# Macropad_BMS.net
KiCad netlist of a schematic drawn in EAGLE
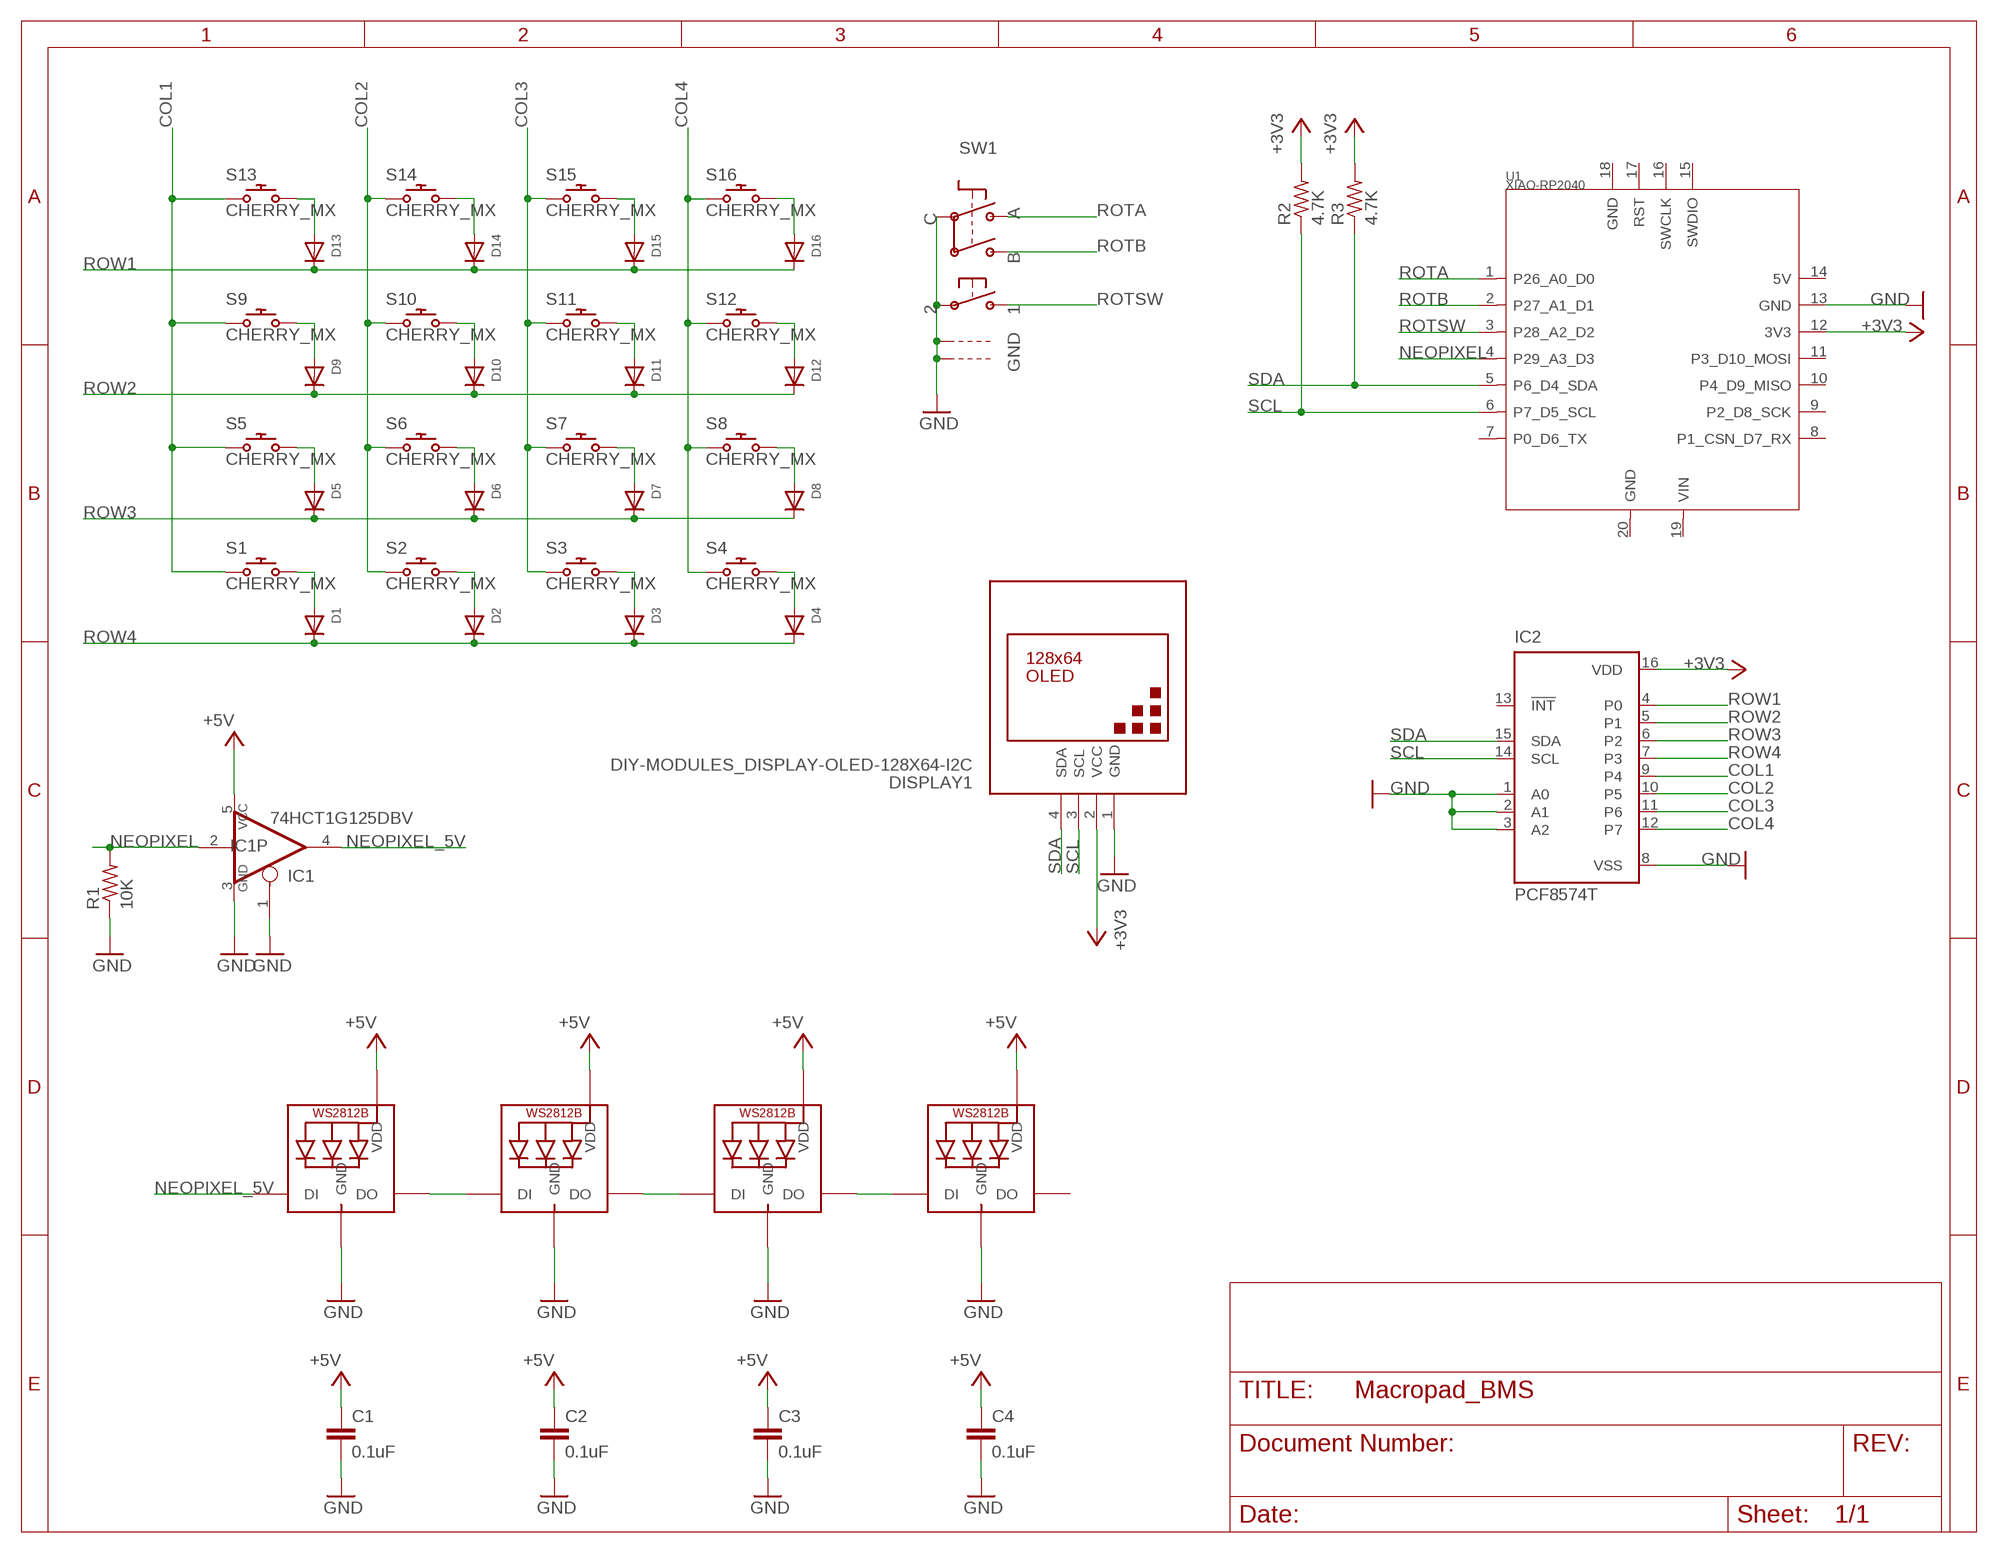
[diagram p0: schematic, sheet 1]

(export (version "E")
  (design (tool "Eeschema 10.0.6"))
  (components
    (comp (ref "C1")
      (value "0.1uF")
      (footprint "eagle-import:0603")
      (libsource (lib "eagle-import") (part "0.1UF-0603-25V-(+80/-20%)"))
    )
    (comp (ref "C2")
      (value "0.1uF")
      (footprint "eagle-import:0603")
      (libsource (lib "eagle-import") (part "0.1UF-0603-25V-(+80/-20%)"))
    )
    (comp (ref "C3")
      (value "0.1uF")
      (footprint "eagle-import:0603")
      (libsource (lib "eagle-import") (part "0.1UF-0603-25V-(+80/-20%)"))
    )
    (comp (ref "C4")
      (value "0.1uF")
      (footprint "eagle-import:0603")
      (libsource (lib "eagle-import") (part "0.1UF-0603-25V-(+80/-20%)"))
    )
    (comp (ref "D1")
      (value "MICROBUILDER_DIODESOD-123")
      (footprint "eagle-import:MICROBUILDER_SOD-123")
      (libsource (lib "eagle-import") (part "MICROBUILDER_DIODESOD-123"))
    )
    (comp (ref "D2")
      (value "MICROBUILDER_DIODESOD-123")
      (footprint "eagle-import:MICROBUILDER_SOD-123")
      (libsource (lib "eagle-import") (part "MICROBUILDER_DIODESOD-123"))
    )
    (comp (ref "D3")
      (value "MICROBUILDER_DIODESOD-123")
      (footprint "eagle-import:MICROBUILDER_SOD-123")
      (libsource (lib "eagle-import") (part "MICROBUILDER_DIODESOD-123"))
    )
    (comp (ref "D4")
      (value "MICROBUILDER_DIODESOD-123")
      (footprint "eagle-import:MICROBUILDER_SOD-123")
      (libsource (lib "eagle-import") (part "MICROBUILDER_DIODESOD-123"))
    )
    (comp (ref "D5")
      (value "MICROBUILDER_DIODESOD-123")
      (footprint "eagle-import:MICROBUILDER_SOD-123")
      (libsource (lib "eagle-import") (part "MICROBUILDER_DIODESOD-123"))
    )
    (comp (ref "D6")
      (value "MICROBUILDER_DIODESOD-123")
      (footprint "eagle-import:MICROBUILDER_SOD-123")
      (libsource (lib "eagle-import") (part "MICROBUILDER_DIODESOD-123"))
    )
    (comp (ref "D7")
      (value "MICROBUILDER_DIODESOD-123")
      (footprint "eagle-import:MICROBUILDER_SOD-123")
      (libsource (lib "eagle-import") (part "MICROBUILDER_DIODESOD-123"))
    )
    (comp (ref "D8")
      (value "MICROBUILDER_DIODESOD-123")
      (footprint "eagle-import:MICROBUILDER_SOD-123")
      (libsource (lib "eagle-import") (part "MICROBUILDER_DIODESOD-123"))
    )
    (comp (ref "D9")
      (value "MICROBUILDER_DIODESOD-123")
      (footprint "eagle-import:MICROBUILDER_SOD-123")
      (libsource (lib "eagle-import") (part "MICROBUILDER_DIODESOD-123"))
    )
    (comp (ref "D10")
      (value "MICROBUILDER_DIODESOD-123")
      (footprint "eagle-import:MICROBUILDER_SOD-123")
      (libsource (lib "eagle-import") (part "MICROBUILDER_DIODESOD-123"))
    )
    (comp (ref "D11")
      (value "MICROBUILDER_DIODESOD-123")
      (footprint "eagle-import:MICROBUILDER_SOD-123")
      (libsource (lib "eagle-import") (part "MICROBUILDER_DIODESOD-123"))
    )
    (comp (ref "D12")
      (value "MICROBUILDER_DIODESOD-123")
      (footprint "eagle-import:MICROBUILDER_SOD-123")
      (libsource (lib "eagle-import") (part "MICROBUILDER_DIODESOD-123"))
    )
    (comp (ref "D13")
      (value "MICROBUILDER_DIODESOD-123")
      (footprint "eagle-import:MICROBUILDER_SOD-123")
      (libsource (lib "eagle-import") (part "MICROBUILDER_DIODESOD-123"))
    )
    (comp (ref "D14")
      (value "MICROBUILDER_DIODESOD-123")
      (footprint "eagle-import:MICROBUILDER_SOD-123")
      (libsource (lib "eagle-import") (part "MICROBUILDER_DIODESOD-123"))
    )
    (comp (ref "D15")
      (value "MICROBUILDER_DIODESOD-123")
      (footprint "eagle-import:MICROBUILDER_SOD-123")
      (libsource (lib "eagle-import") (part "MICROBUILDER_DIODESOD-123"))
    )
    (comp (ref "D16")
      (value "MICROBUILDER_DIODESOD-123")
      (footprint "eagle-import:MICROBUILDER_SOD-123")
      (libsource (lib "eagle-import") (part "MICROBUILDER_DIODESOD-123"))
    )
    (comp (ref "DISPLAY1")
      (value "DIY-MODULES_DISPLAY-OLED-128X64-I2C")
      (footprint "eagle-import:DIY-MODULES_DISPLAY-OLED-128X64-I2C")
      (libsource (lib "eagle-import") (part "DIY-MODULES_DISPLAY-OLED-128X64-I2C"))
    )
    (comp (ref "IC1")
      (value "74HCT1G125DBV")
      (footprint "eagle-import:SOT23-5")
      (libsource (lib "eagle-import") (part "741G125DBVAHC"))
    )
    (comp (ref "IC2")
      (value "PCF8574T")
      (footprint "eagle-import:SO16W")
      (fields (field (name "MPN") "PCF8574T/3,512"))
      (libsource (lib "eagle-import") (part "PCF8574T"))
    )
    (comp (ref "LED1")
      (value "WS2812B5050")
      (footprint "eagle-import:WS2812B")
      (libsource (lib "eagle-import") (part "WS2812B5050"))
    )
    (comp (ref "LED2")
      (value "WS2812B5050")
      (footprint "eagle-import:WS2812B")
      (libsource (lib "eagle-import") (part "WS2812B5050"))
    )
    (comp (ref "LED3")
      (value "WS2812B5050")
      (footprint "eagle-import:WS2812B")
      (libsource (lib "eagle-import") (part "WS2812B5050"))
    )
    (comp (ref "LED4")
      (value "WS2812B5050")
      (footprint "eagle-import:WS2812B")
      (libsource (lib "eagle-import") (part "WS2812B5050"))
    )
    (comp (ref "R1")
      (value "10K")
      (footprint "eagle-import:R0805")
      (libsource (lib "eagle-import") (part "R-US_R0805"))
    )
    (comp (ref "R2")
      (value "4.7K")
      (footprint "eagle-import:R0805")
      (libsource (lib "eagle-import") (part "R-US_R0805"))
    )
    (comp (ref "R3")
      (value "4.7K")
      (footprint "eagle-import:R0805")
      (libsource (lib "eagle-import") (part "R-US_R0805"))
    )
    (comp (ref "S1")
      (value "CHERRY_MX")
      (footprint "eagle-import:CHERRY_MX")
      (libsource (lib "eagle-import") (part "CHERRY_MX"))
    )
    (comp (ref "S2")
      (value "CHERRY_MX")
      (footprint "eagle-import:CHERRY_MX")
      (libsource (lib "eagle-import") (part "CHERRY_MX"))
    )
    (comp (ref "S3")
      (value "CHERRY_MX")
      (footprint "eagle-import:CHERRY_MX")
      (libsource (lib "eagle-import") (part "CHERRY_MX"))
    )
    (comp (ref "S4")
      (value "CHERRY_MX")
      (footprint "eagle-import:CHERRY_MX")
      (libsource (lib "eagle-import") (part "CHERRY_MX"))
    )
    (comp (ref "S5")
      (value "CHERRY_MX")
      (footprint "eagle-import:CHERRY_MX")
      (libsource (lib "eagle-import") (part "CHERRY_MX"))
    )
    (comp (ref "S6")
      (value "CHERRY_MX")
      (footprint "eagle-import:CHERRY_MX")
      (libsource (lib "eagle-import") (part "CHERRY_MX"))
    )
    (comp (ref "S7")
      (value "CHERRY_MX")
      (footprint "eagle-import:CHERRY_MX")
      (libsource (lib "eagle-import") (part "CHERRY_MX"))
    )
    (comp (ref "S8")
      (value "CHERRY_MX")
      (footprint "eagle-import:CHERRY_MX")
      (libsource (lib "eagle-import") (part "CHERRY_MX"))
    )
    (comp (ref "S9")
      (value "CHERRY_MX")
      (footprint "eagle-import:CHERRY_MX")
      (libsource (lib "eagle-import") (part "CHERRY_MX"))
    )
    (comp (ref "S10")
      (value "CHERRY_MX")
      (footprint "eagle-import:CHERRY_MX")
      (libsource (lib "eagle-import") (part "CHERRY_MX"))
    )
    (comp (ref "S11")
      (value "CHERRY_MX")
      (footprint "eagle-import:CHERRY_MX")
      (libsource (lib "eagle-import") (part "CHERRY_MX"))
    )
    (comp (ref "S12")
      (value "CHERRY_MX")
      (footprint "eagle-import:CHERRY_MX")
      (libsource (lib "eagle-import") (part "CHERRY_MX"))
    )
    (comp (ref "S13")
      (value "CHERRY_MX")
      (footprint "eagle-import:CHERRY_MX")
      (libsource (lib "eagle-import") (part "CHERRY_MX"))
    )
    (comp (ref "S14")
      (value "CHERRY_MX")
      (footprint "eagle-import:CHERRY_MX")
      (libsource (lib "eagle-import") (part "CHERRY_MX"))
    )
    (comp (ref "S15")
      (value "CHERRY_MX")
      (footprint "eagle-import:CHERRY_MX")
      (libsource (lib "eagle-import") (part "CHERRY_MX"))
    )
    (comp (ref "S16")
      (value "CHERRY_MX")
      (footprint "eagle-import:CHERRY_MX")
      (libsource (lib "eagle-import") (part "CHERRY_MX"))
    )
    (comp (ref "SW1")
      (value "ADAFRUIT_ELECTROMECH_ENCODER_PLUS_SWITCH_BOURNS_PEC11")
      (footprint "eagle-import:ADAFRUIT_ELECTROMECH_PEC11+SWITCH")
      (libsource (lib "eagle-import") (part "ADAFRUIT_ELECTROMECH_ENCODER_PLUS_SWITCH_PEC11_BOURNS"))
    )
    (comp (ref "U1")
      (value "XIAO-RP2040")
      (footprint "eagle-import:XIAO-SAMD21_RP2040-MODULE14P-2.54-21X17.8MM")
      (libsource (lib "eagle-import") (part "XIAO-RP2040"))
    )
  )
  (nets
    (net (code "1") (name "+3V3") (class "Default")
      (node (ref "DISPLAY1") (pin "2") (pinfunction "VCC_2") (pintype "bidirectional"))
      (node (ref "IC2") (pin "16") (pinfunction "VDD_16") (pintype "power_in"))
      (node (ref "R2") (pin "2") (pinfunction "2_2") (pintype "passive"))
      (node (ref "R3") (pin "2") (pinfunction "2_2") (pintype "passive"))
      (node (ref "U1") (pin "12") (pinfunction "3V3_12") (pintype "bidirectional"))
    )
    (net (code "2") (name "+5V") (class "Default")
      (node (ref "C1") (pin "1") (pinfunction "1_1") (pintype "passive"))
      (node (ref "C2") (pin "1") (pinfunction "1_1") (pintype "passive"))
      (node (ref "C3") (pin "1") (pinfunction "1_1") (pintype "passive"))
      (node (ref "C4") (pin "1") (pinfunction "1_1") (pintype "passive"))
      (node (ref "IC1") (pin "5") (pinfunction "VCC_5") (pintype "power_in"))
      (node (ref "LED1") (pin "1-VDD") (pinfunction "VDD_1-VDD") (pintype "power_in"))
      (node (ref "LED2") (pin "1-VDD") (pinfunction "VDD_1-VDD") (pintype "power_in"))
      (node (ref "LED3") (pin "1-VDD") (pinfunction "VDD_1-VDD") (pintype "power_in"))
      (node (ref "LED4") (pin "1-VDD") (pinfunction "VDD_1-VDD") (pintype "power_in"))
    )
    (net (code "3") (name "/COL1") (class "Default")
      (node (ref "IC2") (pin "9") (pinfunction "P4_9") (pintype "bidirectional"))
      (node (ref "S1") (pin "S1") (pinfunction "1_S1") (pintype "passive"))
      (node (ref "S13") (pin "S1") (pinfunction "1_S1") (pintype "passive"))
      (node (ref "S5") (pin "S1") (pinfunction "1_S1") (pintype "passive"))
      (node (ref "S9") (pin "S1") (pinfunction "1_S1") (pintype "passive"))
    )
    (net (code "4") (name "/COL2") (class "Default")
      (node (ref "IC2") (pin "10") (pinfunction "P5_10") (pintype "bidirectional"))
      (node (ref "S10") (pin "S1") (pinfunction "1_S1") (pintype "passive"))
      (node (ref "S14") (pin "S1") (pinfunction "1_S1") (pintype "passive"))
      (node (ref "S2") (pin "S1") (pinfunction "1_S1") (pintype "passive"))
      (node (ref "S6") (pin "S1") (pinfunction "1_S1") (pintype "passive"))
    )
    (net (code "5") (name "/COL3") (class "Default")
      (node (ref "IC2") (pin "11") (pinfunction "P6_11") (pintype "bidirectional"))
      (node (ref "S11") (pin "S1") (pinfunction "1_S1") (pintype "passive"))
      (node (ref "S15") (pin "S1") (pinfunction "1_S1") (pintype "passive"))
      (node (ref "S3") (pin "S1") (pinfunction "1_S1") (pintype "passive"))
      (node (ref "S7") (pin "S1") (pinfunction "1_S1") (pintype "passive"))
    )
    (net (code "6") (name "/COL4") (class "Default")
      (node (ref "IC2") (pin "12") (pinfunction "P7_12") (pintype "bidirectional"))
      (node (ref "S12") (pin "S1") (pinfunction "1_S1") (pintype "passive"))
      (node (ref "S16") (pin "S1") (pinfunction "1_S1") (pintype "passive"))
      (node (ref "S4") (pin "S1") (pinfunction "1_S1") (pintype "passive"))
      (node (ref "S8") (pin "S1") (pinfunction "1_S1") (pintype "passive"))
    )
    (net (code "7") (name "/NEOPIXEL") (class "Default")
      (node (ref "IC1") (pin "2") (pinfunction "I_2") (pintype "input"))
      (node (ref "R1") (pin "2") (pinfunction "2_2") (pintype "passive"))
      (node (ref "U1") (pin "4") (pinfunction "P29_A3_D3_4") (pintype "bidirectional"))
    )
    (net (code "8") (name "/NEOPIXEL_5V") (class "Default")
      (node (ref "IC1") (pin "4") (pinfunction "O_4") (pintype "tri_state"))
      (node (ref "LED1") (pin "4-DIN") (pinfunction "DI_4-DIN") (pintype "input"))
    )
    (net (code "9") (name "/ROTA") (class "Default")
      (node (ref "SW1") (pin "P$A") (pinfunction "P$A_P$A") (pintype "passive"))
      (node (ref "U1") (pin "1") (pinfunction "P26_A0_D0_1") (pintype "bidirectional"))
    )
    (net (code "10") (name "/ROTB") (class "Default")
      (node (ref "SW1") (pin "P$B") (pinfunction "P$B_P$B") (pintype "passive"))
      (node (ref "U1") (pin "2") (pinfunction "P27_A1_D1_2") (pintype "bidirectional"))
    )
    (net (code "11") (name "/ROTSW") (class "Default")
      (node (ref "SW1") (pin "P$1") (pinfunction "P$1_P$1") (pintype "passive"))
      (node (ref "U1") (pin "3") (pinfunction "P28_A2_D2_3") (pintype "bidirectional"))
    )
    (net (code "12") (name "/ROW1") (class "Default")
      (node (ref "D13") (pin "C") (pinfunction "C_C") (pintype "passive"))
      (node (ref "D14") (pin "C") (pinfunction "C_C") (pintype "passive"))
      (node (ref "D15") (pin "C") (pinfunction "C_C") (pintype "passive"))
      (node (ref "D16") (pin "C") (pinfunction "C_C") (pintype "passive"))
      (node (ref "IC2") (pin "4") (pinfunction "P0_4") (pintype "bidirectional"))
    )
    (net (code "13") (name "/ROW2") (class "Default")
      (node (ref "D10") (pin "C") (pinfunction "C_C") (pintype "passive"))
      (node (ref "D11") (pin "C") (pinfunction "C_C") (pintype "passive"))
      (node (ref "D12") (pin "C") (pinfunction "C_C") (pintype "passive"))
      (node (ref "D9") (pin "C") (pinfunction "C_C") (pintype "passive"))
      (node (ref "IC2") (pin "5") (pinfunction "P1_5") (pintype "bidirectional"))
    )
    (net (code "14") (name "/ROW3") (class "Default")
      (node (ref "D5") (pin "C") (pinfunction "C_C") (pintype "passive"))
      (node (ref "D6") (pin "C") (pinfunction "C_C") (pintype "passive"))
      (node (ref "D7") (pin "C") (pinfunction "C_C") (pintype "passive"))
      (node (ref "D8") (pin "C") (pinfunction "C_C") (pintype "passive"))
      (node (ref "IC2") (pin "6") (pinfunction "P2_6") (pintype "bidirectional"))
    )
    (net (code "15") (name "/ROW4") (class "Default")
      (node (ref "D1") (pin "C") (pinfunction "C_C") (pintype "passive"))
      (node (ref "D2") (pin "C") (pinfunction "C_C") (pintype "passive"))
      (node (ref "D3") (pin "C") (pinfunction "C_C") (pintype "passive"))
      (node (ref "D4") (pin "C") (pinfunction "C_C") (pintype "passive"))
      (node (ref "IC2") (pin "7") (pinfunction "P3_7") (pintype "bidirectional"))
    )
    (net (code "16") (name "/SCL") (class "Default")
      (node (ref "DISPLAY1") (pin "3") (pinfunction "SCL_3") (pintype "bidirectional"))
      (node (ref "IC2") (pin "14") (pinfunction "SCL_14") (pintype "input"))
      (node (ref "R2") (pin "1") (pinfunction "1_1") (pintype "passive"))
      (node (ref "U1") (pin "6") (pinfunction "P7_D5_SCL_6") (pintype "bidirectional"))
    )
    (net (code "17") (name "/SDA") (class "Default")
      (node (ref "DISPLAY1") (pin "4") (pinfunction "SDA_4") (pintype "bidirectional"))
      (node (ref "IC2") (pin "15") (pinfunction "SDA_15") (pintype "bidirectional"))
      (node (ref "R3") (pin "1") (pinfunction "1_1") (pintype "passive"))
      (node (ref "U1") (pin "5") (pinfunction "P6_D4_SDA_5") (pintype "bidirectional"))
    )
    (net (code "18") (name "GND") (class "Default")
      (node (ref "C1") (pin "2") (pinfunction "2_2") (pintype "passive"))
      (node (ref "C2") (pin "2") (pinfunction "2_2") (pintype "passive"))
      (node (ref "C3") (pin "2") (pinfunction "2_2") (pintype "passive"))
      (node (ref "C4") (pin "2") (pinfunction "2_2") (pintype "passive"))
      (node (ref "DISPLAY1") (pin "1") (pinfunction "GND_1") (pintype "bidirectional"))
      (node (ref "IC1") (pin "1") (pinfunction "OE_1") (pintype "input"))
      (node (ref "IC1") (pin "3") (pinfunction "GND_3") (pintype "power_in"))
      (node (ref "IC2") (pin "1") (pinfunction "A0_1") (pintype "input"))
      (node (ref "IC2") (pin "2") (pinfunction "A1_2") (pintype "input"))
      (node (ref "IC2") (pin "3") (pinfunction "A2_3") (pintype "input"))
      (node (ref "IC2") (pin "8") (pinfunction "VSS_8") (pintype "power_in"))
      (node (ref "LED1") (pin "3-GND") (pinfunction "GND_3-GND") (pintype "power_in"))
      (node (ref "LED2") (pin "3-GND") (pinfunction "GND_3-GND") (pintype "power_in"))
      (node (ref "LED3") (pin "3-GND") (pinfunction "GND_3-GND") (pintype "power_in"))
      (node (ref "LED4") (pin "3-GND") (pinfunction "GND_3-GND") (pintype "power_in"))
      (node (ref "R1") (pin "1") (pinfunction "1_1") (pintype "passive"))
      (node (ref "SW1") (pin "P$2") (pinfunction "P$2_P$2") (pintype "passive"))
      (node (ref "SW1") (pin "P$C") (pinfunction "P$C_P$C") (pintype "passive"))
      (node (ref "SW1") (pin "P$GND1") (pinfunction "P$GND1_P$GND1") (pintype "passive"))
      (node (ref "SW1") (pin "P$GND2") (pinfunction "P$GND2_P$GND2") (pintype "passive"))
      (node (ref "U1") (pin "13") (pinfunction "GND_13") (pintype "bidirectional"))
    )
    (net (code "19") (name "Net-(LED1-DO)") (class "Default")
      (node (ref "LED1") (pin "2-DOUT") (pinfunction "DO_2-DOUT") (pintype "output"))
      (node (ref "LED2") (pin "4-DIN") (pinfunction "DI_4-DIN") (pintype "input"))
    )
    (net (code "20") (name "Net-(LED2-DO)") (class "Default")
      (node (ref "LED2") (pin "2-DOUT") (pinfunction "DO_2-DOUT") (pintype "output"))
      (node (ref "LED3") (pin "4-DIN") (pinfunction "DI_4-DIN") (pintype "input"))
    )
    (net (code "21") (name "Net-(LED3-DO)") (class "Default")
      (node (ref "LED3") (pin "2-DOUT") (pinfunction "DO_2-DOUT") (pintype "output"))
      (node (ref "LED4") (pin "4-DIN") (pinfunction "DI_4-DIN") (pintype "input"))
    )
    (net (code "22") (name "Net-(S1-2)") (class "Default")
      (node (ref "D1") (pin "A") (pinfunction "A_A") (pintype "passive"))
      (node (ref "S1") (pin "S2") (pinfunction "2_S2") (pintype "passive"))
    )
    (net (code "23") (name "Net-(S2-2)") (class "Default")
      (node (ref "D2") (pin "A") (pinfunction "A_A") (pintype "passive"))
      (node (ref "S2") (pin "S2") (pinfunction "2_S2") (pintype "passive"))
    )
    (net (code "24") (name "Net-(S3-2)") (class "Default")
      (node (ref "D3") (pin "A") (pinfunction "A_A") (pintype "passive"))
      (node (ref "S3") (pin "S2") (pinfunction "2_S2") (pintype "passive"))
    )
    (net (code "25") (name "Net-(S4-2)") (class "Default")
      (node (ref "D4") (pin "A") (pinfunction "A_A") (pintype "passive"))
      (node (ref "S4") (pin "S2") (pinfunction "2_S2") (pintype "passive"))
    )
    (net (code "26") (name "Net-(S5-2)") (class "Default")
      (node (ref "D5") (pin "A") (pinfunction "A_A") (pintype "passive"))
      (node (ref "S5") (pin "S2") (pinfunction "2_S2") (pintype "passive"))
    )
    (net (code "27") (name "Net-(S6-2)") (class "Default")
      (node (ref "D6") (pin "A") (pinfunction "A_A") (pintype "passive"))
      (node (ref "S6") (pin "S2") (pinfunction "2_S2") (pintype "passive"))
    )
    (net (code "28") (name "Net-(S7-2)") (class "Default")
      (node (ref "D7") (pin "A") (pinfunction "A_A") (pintype "passive"))
      (node (ref "S7") (pin "S2") (pinfunction "2_S2") (pintype "passive"))
    )
    (net (code "29") (name "Net-(S8-2)") (class "Default")
      (node (ref "D8") (pin "A") (pinfunction "A_A") (pintype "passive"))
      (node (ref "S8") (pin "S2") (pinfunction "2_S2") (pintype "passive"))
    )
    (net (code "30") (name "Net-(S9-2)") (class "Default")
      (node (ref "D9") (pin "A") (pinfunction "A_A") (pintype "passive"))
      (node (ref "S9") (pin "S2") (pinfunction "2_S2") (pintype "passive"))
    )
    (net (code "31") (name "Net-(S10-2)") (class "Default")
      (node (ref "D10") (pin "A") (pinfunction "A_A") (pintype "passive"))
      (node (ref "S10") (pin "S2") (pinfunction "2_S2") (pintype "passive"))
    )
    (net (code "32") (name "Net-(S11-2)") (class "Default")
      (node (ref "D11") (pin "A") (pinfunction "A_A") (pintype "passive"))
      (node (ref "S11") (pin "S2") (pinfunction "2_S2") (pintype "passive"))
    )
    (net (code "33") (name "Net-(S12-2)") (class "Default")
      (node (ref "D12") (pin "A") (pinfunction "A_A") (pintype "passive"))
      (node (ref "S12") (pin "S2") (pinfunction "2_S2") (pintype "passive"))
    )
    (net (code "34") (name "Net-(S13-2)") (class "Default")
      (node (ref "D13") (pin "A") (pinfunction "A_A") (pintype "passive"))
      (node (ref "S13") (pin "S2") (pinfunction "2_S2") (pintype "passive"))
    )
    (net (code "35") (name "Net-(S14-2)") (class "Default")
      (node (ref "D14") (pin "A") (pinfunction "A_A") (pintype "passive"))
      (node (ref "S14") (pin "S2") (pinfunction "2_S2") (pintype "passive"))
    )
    (net (code "36") (name "Net-(S15-2)") (class "Default")
      (node (ref "D15") (pin "A") (pinfunction "A_A") (pintype "passive"))
      (node (ref "S15") (pin "S2") (pinfunction "2_S2") (pintype "passive"))
    )
    (net (code "37") (name "Net-(S16-2)") (class "Default")
      (node (ref "D16") (pin "A") (pinfunction "A_A") (pintype "passive"))
      (node (ref "S16") (pin "S2") (pinfunction "2_S2") (pintype "passive"))
    )
    (net (code "38") (name "unconnected-(IC2-~{INT}-Pad13)") (class "Default")
      (node (ref "IC2") (pin "13") (pinfunction "~{INT}_13") (pintype "output"))
    )
    (net (code "39") (name "unconnected-(LED4-DO-Pad2-DOUT)") (class "Default")
      (node (ref "LED4") (pin "2-DOUT") (pinfunction "DO_2-DOUT") (pintype "output"))
    )
    (net (code "40") (name "unconnected-(U1-5V-Pad14)") (class "Default")
      (node (ref "U1") (pin "14") (pinfunction "5V_14") (pintype "bidirectional"))
    )
    (net (code "41") (name "unconnected-(U1-GND-Pad18)") (class "Default")
      (node (ref "U1") (pin "18") (pinfunction "GND_18") (pintype "bidirectional"))
    )
    (net (code "42") (name "unconnected-(U1-GND-Pad20)") (class "Default")
      (node (ref "U1") (pin "20") (pinfunction "GND_20") (pintype "bidirectional"))
    )
    (net (code "43") (name "unconnected-(U1-P0_D6_TX-Pad7)") (class "Default")
      (node (ref "U1") (pin "7") (pinfunction "P0_D6_TX_7") (pintype "bidirectional"))
    )
    (net (code "44") (name "unconnected-(U1-P1_CSN_D7_RX-Pad8)") (class "Default")
      (node (ref "U1") (pin "8") (pinfunction "P1_CSN_D7_RX_8") (pintype "bidirectional"))
    )
    (net (code "45") (name "unconnected-(U1-P2_D8_SCK-Pad9)") (class "Default")
      (node (ref "U1") (pin "9") (pinfunction "P2_D8_SCK_9") (pintype "bidirectional"))
    )
    (net (code "46") (name "unconnected-(U1-P3_D10_MOSI-Pad11)") (class "Default")
      (node (ref "U1") (pin "11") (pinfunction "P3_D10_MOSI_11") (pintype "bidirectional"))
    )
    (net (code "47") (name "unconnected-(U1-P4_D9_MISO-Pad10)") (class "Default")
      (node (ref "U1") (pin "10") (pinfunction "P4_D9_MISO_10") (pintype "bidirectional"))
    )
    (net (code "48") (name "unconnected-(U1-RST-Pad17)") (class "Default")
      (node (ref "U1") (pin "17") (pinfunction "RST_17") (pintype "bidirectional"))
    )
    (net (code "49") (name "unconnected-(U1-SWCLK-Pad16)") (class "Default")
      (node (ref "U1") (pin "16") (pinfunction "SWCLK_16") (pintype "bidirectional"))
    )
    (net (code "50") (name "unconnected-(U1-SWDIO-Pad15)") (class "Default")
      (node (ref "U1") (pin "15") (pinfunction "SWDIO_15") (pintype "bidirectional"))
    )
    (net (code "51") (name "unconnected-(U1-VIN-Pad19)") (class "Default")
      (node (ref "U1") (pin "19") (pinfunction "VIN_19") (pintype "bidirectional"))
    )
  )
)
